# scheme_hydra_power.net
KiCad netlist of a schematic drawn in Altium Designer
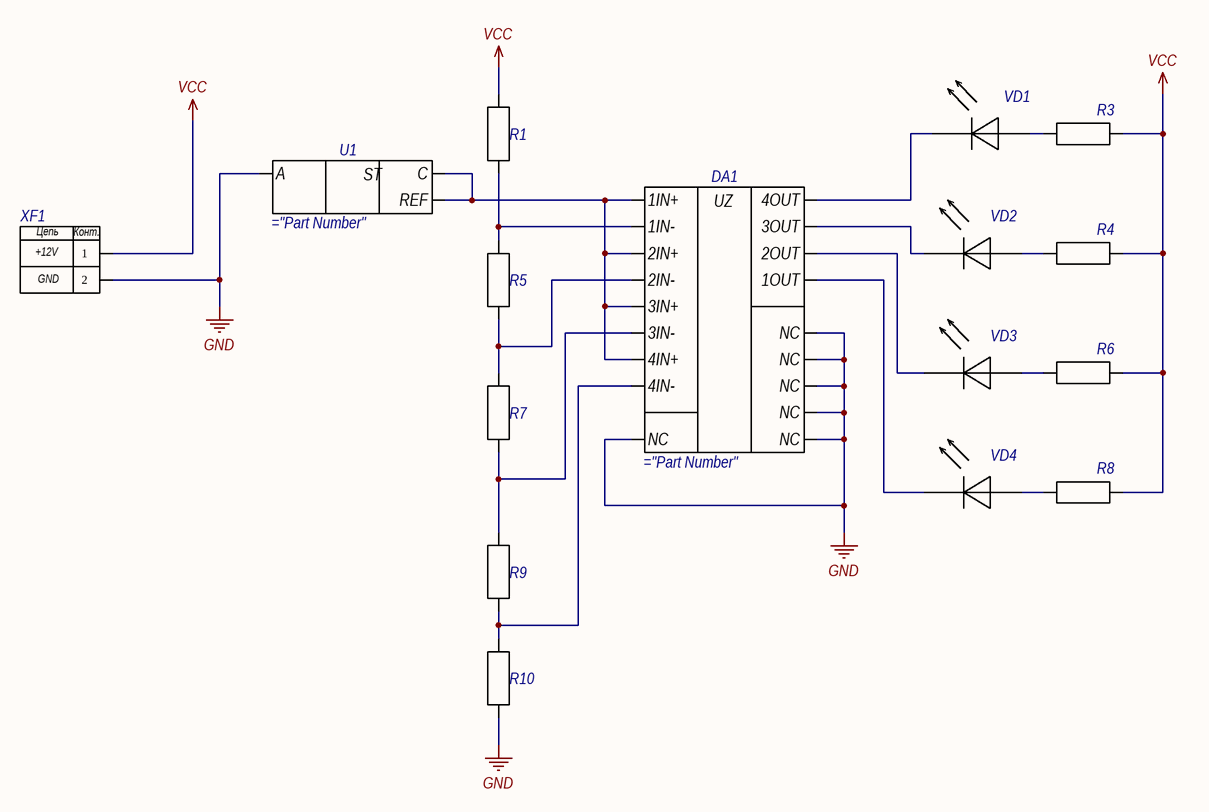
[diagram p0: scheme_hydra_power.SchDoc]

(export (version "E")
  (design (tool "Eeschema 10.0.6"))
  (components
    (comp (ref "DA1") (value "~") (libsource (lib "Hydrolib") (part "LM139")))
    (comp (ref "R1") (value "R") (libsource (lib "Hydrolib") (part "R")))
    (comp (ref "R3") (value "R") (libsource (lib "") (part "R_1")))
    (comp (ref "R4") (value "R") (libsource (lib "") (part "R_1")))
    (comp (ref "R5") (value "R") (libsource (lib "Hydrolib") (part "R")))
    (comp (ref "R6") (value "R") (libsource (lib "") (part "R_1")))
    (comp (ref "R7") (value "R") (libsource (lib "Hydrolib") (part "R")))
    (comp (ref "R8") (value "R") (libsource (lib "") (part "R_1")))
    (comp (ref "R9") (value "R") (libsource (lib "Hydrolib") (part "R")))
    (comp (ref "R10") (value "R") (libsource (lib "Hydrolib") (part "R")))
    (comp (ref "U1") (value "~") (libsource (lib "Hydrolib") (part "TLA431")))
    (comp (ref "VD1") (value "Led_diod") (libsource (lib "Hydrolib") (part "Led_diod")))
    (comp (ref "VD2") (value "Led_diod") (libsource (lib "Hydrolib") (part "Led_diod")))
    (comp (ref "VD3") (value "Led_diod") (libsource (lib "Hydrolib") (part "Led_diod")))
    (comp (ref "VD4") (value "Led_diod") (libsource (lib "Hydrolib") (part "Led_diod")))
    (comp (ref "XF1") (value "PIN_POWER") (libsource (lib "Hydrolib") (part "PIN_POWER")))
  )
  (nets
    (net (code "1") (name "GND") (class "Default")
      (node (ref "DA1") (pin "1") (pinfunction "NC_1") (pintype "passive"))
      (node (ref "DA1") (pin "11") (pinfunction "NC_11") (pintype "passive"))
      (node (ref "DA1") (pin "15") (pinfunction "NC_15") (pintype "passive"))
      (node (ref "DA1") (pin "17") (pinfunction "NC_17") (pintype "passive"))
      (node (ref "DA1") (pin "5") (pinfunction "NC_5") (pintype "passive"))
      (node (ref "DA1") (pin "7") (pinfunction "NC_7") (pintype "passive"))
      (node (ref "R10") (pin "1") (pinfunction "1_1") (pintype "passive"))
      (node (ref "U1") (pin "3") (pinfunction "A_3") (pintype "passive"))
      (node (ref "XF1") (pin "2") (pinfunction "2_2") (pintype "passive"))
    )
    (net (code "2") (name "Net-(DA1-1IN+)") (class "Default")
      (node (ref "DA1") (pin "10") (pinfunction "1IN+_10") (pintype "passive"))
      (node (ref "DA1") (pin "13") (pinfunction "3IN+_13") (pintype "passive"))
      (node (ref "DA1") (pin "16") (pinfunction "4IN+_16") (pintype "passive"))
      (node (ref "DA1") (pin "8") (pinfunction "2IN+_8") (pintype "passive"))
      (node (ref "U1") (pin "1") (pinfunction "C_1") (pintype "passive"))
      (node (ref "U1") (pin "2") (pinfunction "REF_2") (pintype "passive"))
    )
    (net (code "3") (name "Net-(DA1-1IN-)") (class "Default")
      (node (ref "DA1") (pin "9") (pinfunction "1IN-_9") (pintype "passive"))
      (node (ref "R1") (pin "1") (pinfunction "1_1") (pintype "passive"))
      (node (ref "R5") (pin "2") (pinfunction "2_2") (pintype "passive"))
    )
    (net (code "4") (name "Net-(DA1-1OUT)") (class "Default")
      (node (ref "DA1") (pin "2") (pinfunction "1OUT_2") (pintype "passive"))
      (node (ref "VD4") (pin "2") (pinfunction "2_2") (pintype "passive"))
    )
    (net (code "5") (name "Net-(DA1-2IN-)") (class "Default")
      (node (ref "DA1") (pin "6") (pinfunction "2IN-_6") (pintype "passive"))
      (node (ref "R5") (pin "1") (pinfunction "1_1") (pintype "passive"))
      (node (ref "R7") (pin "2") (pinfunction "2_2") (pintype "passive"))
    )
    (net (code "6") (name "Net-(DA1-2OUT)") (class "Default")
      (node (ref "DA1") (pin "3") (pinfunction "2OUT_3") (pintype "passive"))
      (node (ref "VD3") (pin "2") (pinfunction "2_2") (pintype "passive"))
    )
    (net (code "7") (name "Net-(DA1-3IN-)") (class "Default")
      (node (ref "DA1") (pin "12") (pinfunction "3IN-_12") (pintype "passive"))
      (node (ref "R7") (pin "1") (pinfunction "1_1") (pintype "passive"))
      (node (ref "R9") (pin "2") (pinfunction "2_2") (pintype "passive"))
    )
    (net (code "8") (name "Net-(DA1-3OUT)") (class "Default")
      (node (ref "DA1") (pin "20") (pinfunction "3OUT_20") (pintype "passive"))
      (node (ref "VD2") (pin "2") (pinfunction "2_2") (pintype "passive"))
    )
    (net (code "9") (name "Net-(DA1-4IN-)") (class "Default")
      (node (ref "DA1") (pin "14") (pinfunction "4IN-_14") (pintype "passive"))
      (node (ref "R10") (pin "2") (pinfunction "2_2") (pintype "passive"))
      (node (ref "R9") (pin "1") (pinfunction "1_1") (pintype "passive"))
    )
    (net (code "10") (name "Net-(DA1-4OUT)") (class "Default")
      (node (ref "DA1") (pin "19") (pinfunction "4OUT_19") (pintype "passive"))
      (node (ref "VD1") (pin "2") (pinfunction "2_2") (pintype "passive"))
    )
    (net (code "11") (name "Net-(R3-Pad1)") (class "Default")
      (node (ref "R3") (pin "1") (pinfunction "1_1") (pintype "passive"))
      (node (ref "VD1") (pin "1") (pinfunction "1_1") (pintype "passive"))
    )
    (net (code "12") (name "Net-(R4-Pad1)") (class "Default")
      (node (ref "R4") (pin "1") (pinfunction "1_1") (pintype "passive"))
      (node (ref "VD2") (pin "1") (pinfunction "1_1") (pintype "passive"))
    )
    (net (code "13") (name "Net-(R6-Pad1)") (class "Default")
      (node (ref "R6") (pin "1") (pinfunction "1_1") (pintype "passive"))
      (node (ref "VD3") (pin "1") (pinfunction "1_1") (pintype "passive"))
    )
    (net (code "14") (name "Net-(R8-Pad1)") (class "Default")
      (node (ref "R8") (pin "1") (pinfunction "1_1") (pintype "passive"))
      (node (ref "VD4") (pin "1") (pinfunction "1_1") (pintype "passive"))
    )
    (net (code "15") (name "VCC") (class "Default")
      (node (ref "R1") (pin "2") (pinfunction "2_2") (pintype "passive"))
      (node (ref "R3") (pin "2") (pinfunction "2_2") (pintype "passive"))
      (node (ref "R4") (pin "2") (pinfunction "2_2") (pintype "passive"))
      (node (ref "R6") (pin "2") (pinfunction "2_2") (pintype "passive"))
      (node (ref "R8") (pin "2") (pinfunction "2_2") (pintype "passive"))
      (node (ref "XF1") (pin "1") (pinfunction "1_1") (pintype "passive"))
    )
    (net (code "16") (name "unconnected-(DA1-GND-Pad18)") (class "Default")
      (node (ref "DA1") (pin "18") (pinfunction "GND_18") (pintype "passive"))
    )
    (net (code "17") (name "unconnected-(DA1-VCC-Pad4)") (class "Default")
      (node (ref "DA1") (pin "4") (pinfunction "VCC_4") (pintype "passive"))
    )
  )
)
